# Extend.net
KiCad netlist of a schematic drawn in Altium Designer
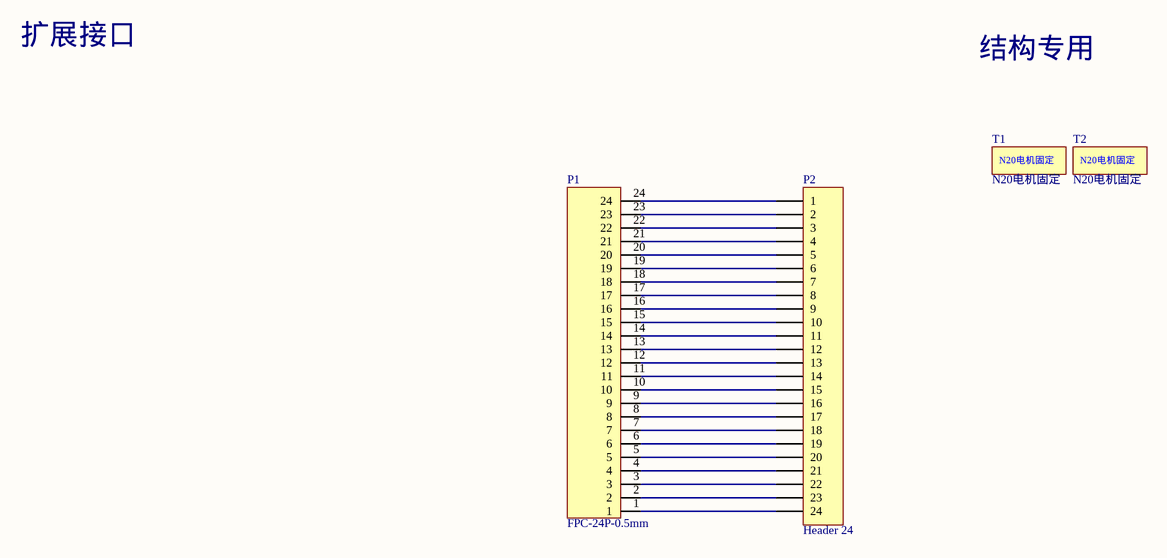
[diagram p0: Extend.SchDoc]

(export (version "E")
  (design (tool "Eeschema 10.0.6"))
  (components
    (comp (ref "P1")
      (value "FPC-24P-0.5mm")
      (footprint "FPC24-0.5mm")
      (libsource (lib "Yang_Lib") (part "FPC-24-0.5mm"))
    )
    (comp (ref "P2")
      (value "Header 24")
      (footprint "HDR1X24")
      (description "Header, 24-Pin")
      (fields (field (name "PUBLISHER") "Altium Limited"))
      (libsource (lib "Miscellaneous Connectors") (part "Header 24"))
    )
    (comp (ref "T1") (value "N20电机固定") (footprint "MOTO") (libsource (lib "Yang_Lib") (part "N20电机固定")))
    (comp (ref "T2") (value "N20电机固定") (footprint "MOTO") (libsource (lib "Yang_Lib") (part "N20电机固定")))
  )
  (nets
    (net (code "1") (name "Net-(P1-Pad1)") (class "Default")
      (node (ref "P1") (pin "1") (pinfunction "1_1") (pintype "passive"))
      (node (ref "P2") (pin "24") (pinfunction "24_24") (pintype "passive"))
    )
    (net (code "2") (name "Net-(P1-Pad2)") (class "Default")
      (node (ref "P1") (pin "2") (pinfunction "2_2") (pintype "passive"))
      (node (ref "P2") (pin "23") (pinfunction "23_23") (pintype "passive"))
    )
    (net (code "3") (name "Net-(P1-Pad3)") (class "Default")
      (node (ref "P1") (pin "3") (pinfunction "3_3") (pintype "passive"))
      (node (ref "P2") (pin "22") (pinfunction "22_22") (pintype "passive"))
    )
    (net (code "4") (name "Net-(P1-Pad4)") (class "Default")
      (node (ref "P1") (pin "4") (pinfunction "4_4") (pintype "passive"))
      (node (ref "P2") (pin "21") (pinfunction "21_21") (pintype "passive"))
    )
    (net (code "5") (name "Net-(P1-Pad5)") (class "Default")
      (node (ref "P1") (pin "5") (pinfunction "5_5") (pintype "passive"))
      (node (ref "P2") (pin "20") (pinfunction "20_20") (pintype "passive"))
    )
    (net (code "6") (name "Net-(P1-Pad6)") (class "Default")
      (node (ref "P1") (pin "6") (pinfunction "6_6") (pintype "passive"))
      (node (ref "P2") (pin "19") (pinfunction "19_19") (pintype "passive"))
    )
    (net (code "7") (name "Net-(P1-Pad7)") (class "Default")
      (node (ref "P1") (pin "7") (pinfunction "7_7") (pintype "passive"))
      (node (ref "P2") (pin "18") (pinfunction "18_18") (pintype "passive"))
    )
    (net (code "8") (name "Net-(P1-Pad8)") (class "Default")
      (node (ref "P1") (pin "8") (pinfunction "8_8") (pintype "passive"))
      (node (ref "P2") (pin "17") (pinfunction "17_17") (pintype "passive"))
    )
    (net (code "9") (name "Net-(P1-Pad9)") (class "Default")
      (node (ref "P1") (pin "9") (pinfunction "9_9") (pintype "passive"))
      (node (ref "P2") (pin "16") (pinfunction "16_16") (pintype "passive"))
    )
    (net (code "10") (name "Net-(P1-Pad10)") (class "Default")
      (node (ref "P1") (pin "10") (pinfunction "10_10") (pintype "passive"))
      (node (ref "P2") (pin "15") (pinfunction "15_15") (pintype "passive"))
    )
    (net (code "11") (name "Net-(P1-Pad11)") (class "Default")
      (node (ref "P1") (pin "11") (pinfunction "11_11") (pintype "passive"))
      (node (ref "P2") (pin "14") (pinfunction "14_14") (pintype "passive"))
    )
    (net (code "12") (name "Net-(P1-Pad12)") (class "Default")
      (node (ref "P1") (pin "12") (pinfunction "12_12") (pintype "passive"))
      (node (ref "P2") (pin "13") (pinfunction "13_13") (pintype "passive"))
    )
    (net (code "13") (name "Net-(P1-Pad13)") (class "Default")
      (node (ref "P1") (pin "13") (pinfunction "13_13") (pintype "passive"))
      (node (ref "P2") (pin "12") (pinfunction "12_12") (pintype "passive"))
    )
    (net (code "14") (name "Net-(P1-Pad14)") (class "Default")
      (node (ref "P1") (pin "14") (pinfunction "14_14") (pintype "passive"))
      (node (ref "P2") (pin "11") (pinfunction "11_11") (pintype "passive"))
    )
    (net (code "15") (name "Net-(P1-Pad15)") (class "Default")
      (node (ref "P1") (pin "15") (pinfunction "15_15") (pintype "passive"))
      (node (ref "P2") (pin "10") (pinfunction "10_10") (pintype "passive"))
    )
    (net (code "16") (name "Net-(P1-Pad16)") (class "Default")
      (node (ref "P1") (pin "16") (pinfunction "16_16") (pintype "passive"))
      (node (ref "P2") (pin "9") (pinfunction "9_9") (pintype "passive"))
    )
    (net (code "17") (name "Net-(P1-Pad17)") (class "Default")
      (node (ref "P1") (pin "17") (pinfunction "17_17") (pintype "passive"))
      (node (ref "P2") (pin "8") (pinfunction "8_8") (pintype "passive"))
    )
    (net (code "18") (name "Net-(P1-Pad18)") (class "Default")
      (node (ref "P1") (pin "18") (pinfunction "18_18") (pintype "passive"))
      (node (ref "P2") (pin "7") (pinfunction "7_7") (pintype "passive"))
    )
    (net (code "19") (name "Net-(P1-Pad19)") (class "Default")
      (node (ref "P1") (pin "19") (pinfunction "19_19") (pintype "passive"))
      (node (ref "P2") (pin "6") (pinfunction "6_6") (pintype "passive"))
    )
    (net (code "20") (name "Net-(P1-Pad20)") (class "Default")
      (node (ref "P1") (pin "20") (pinfunction "20_20") (pintype "passive"))
      (node (ref "P2") (pin "5") (pinfunction "5_5") (pintype "passive"))
    )
    (net (code "21") (name "Net-(P1-Pad21)") (class "Default")
      (node (ref "P1") (pin "21") (pinfunction "21_21") (pintype "passive"))
      (node (ref "P2") (pin "4") (pinfunction "4_4") (pintype "passive"))
    )
    (net (code "22") (name "Net-(P1-Pad22)") (class "Default")
      (node (ref "P1") (pin "22") (pinfunction "22_22") (pintype "passive"))
      (node (ref "P2") (pin "3") (pinfunction "3_3") (pintype "passive"))
    )
    (net (code "23") (name "Net-(P1-Pad23)") (class "Default")
      (node (ref "P1") (pin "23") (pinfunction "23_23") (pintype "passive"))
      (node (ref "P2") (pin "2") (pinfunction "2_2") (pintype "passive"))
    )
    (net (code "24") (name "Net-(P1-Pad24)") (class "Default")
      (node (ref "P1") (pin "24") (pinfunction "24_24") (pintype "passive"))
      (node (ref "P2") (pin "1") (pinfunction "1_1") (pintype "passive"))
    )
  )
)
